# Nyan.net
KiCad netlist of a schematic drawn in EAGLE
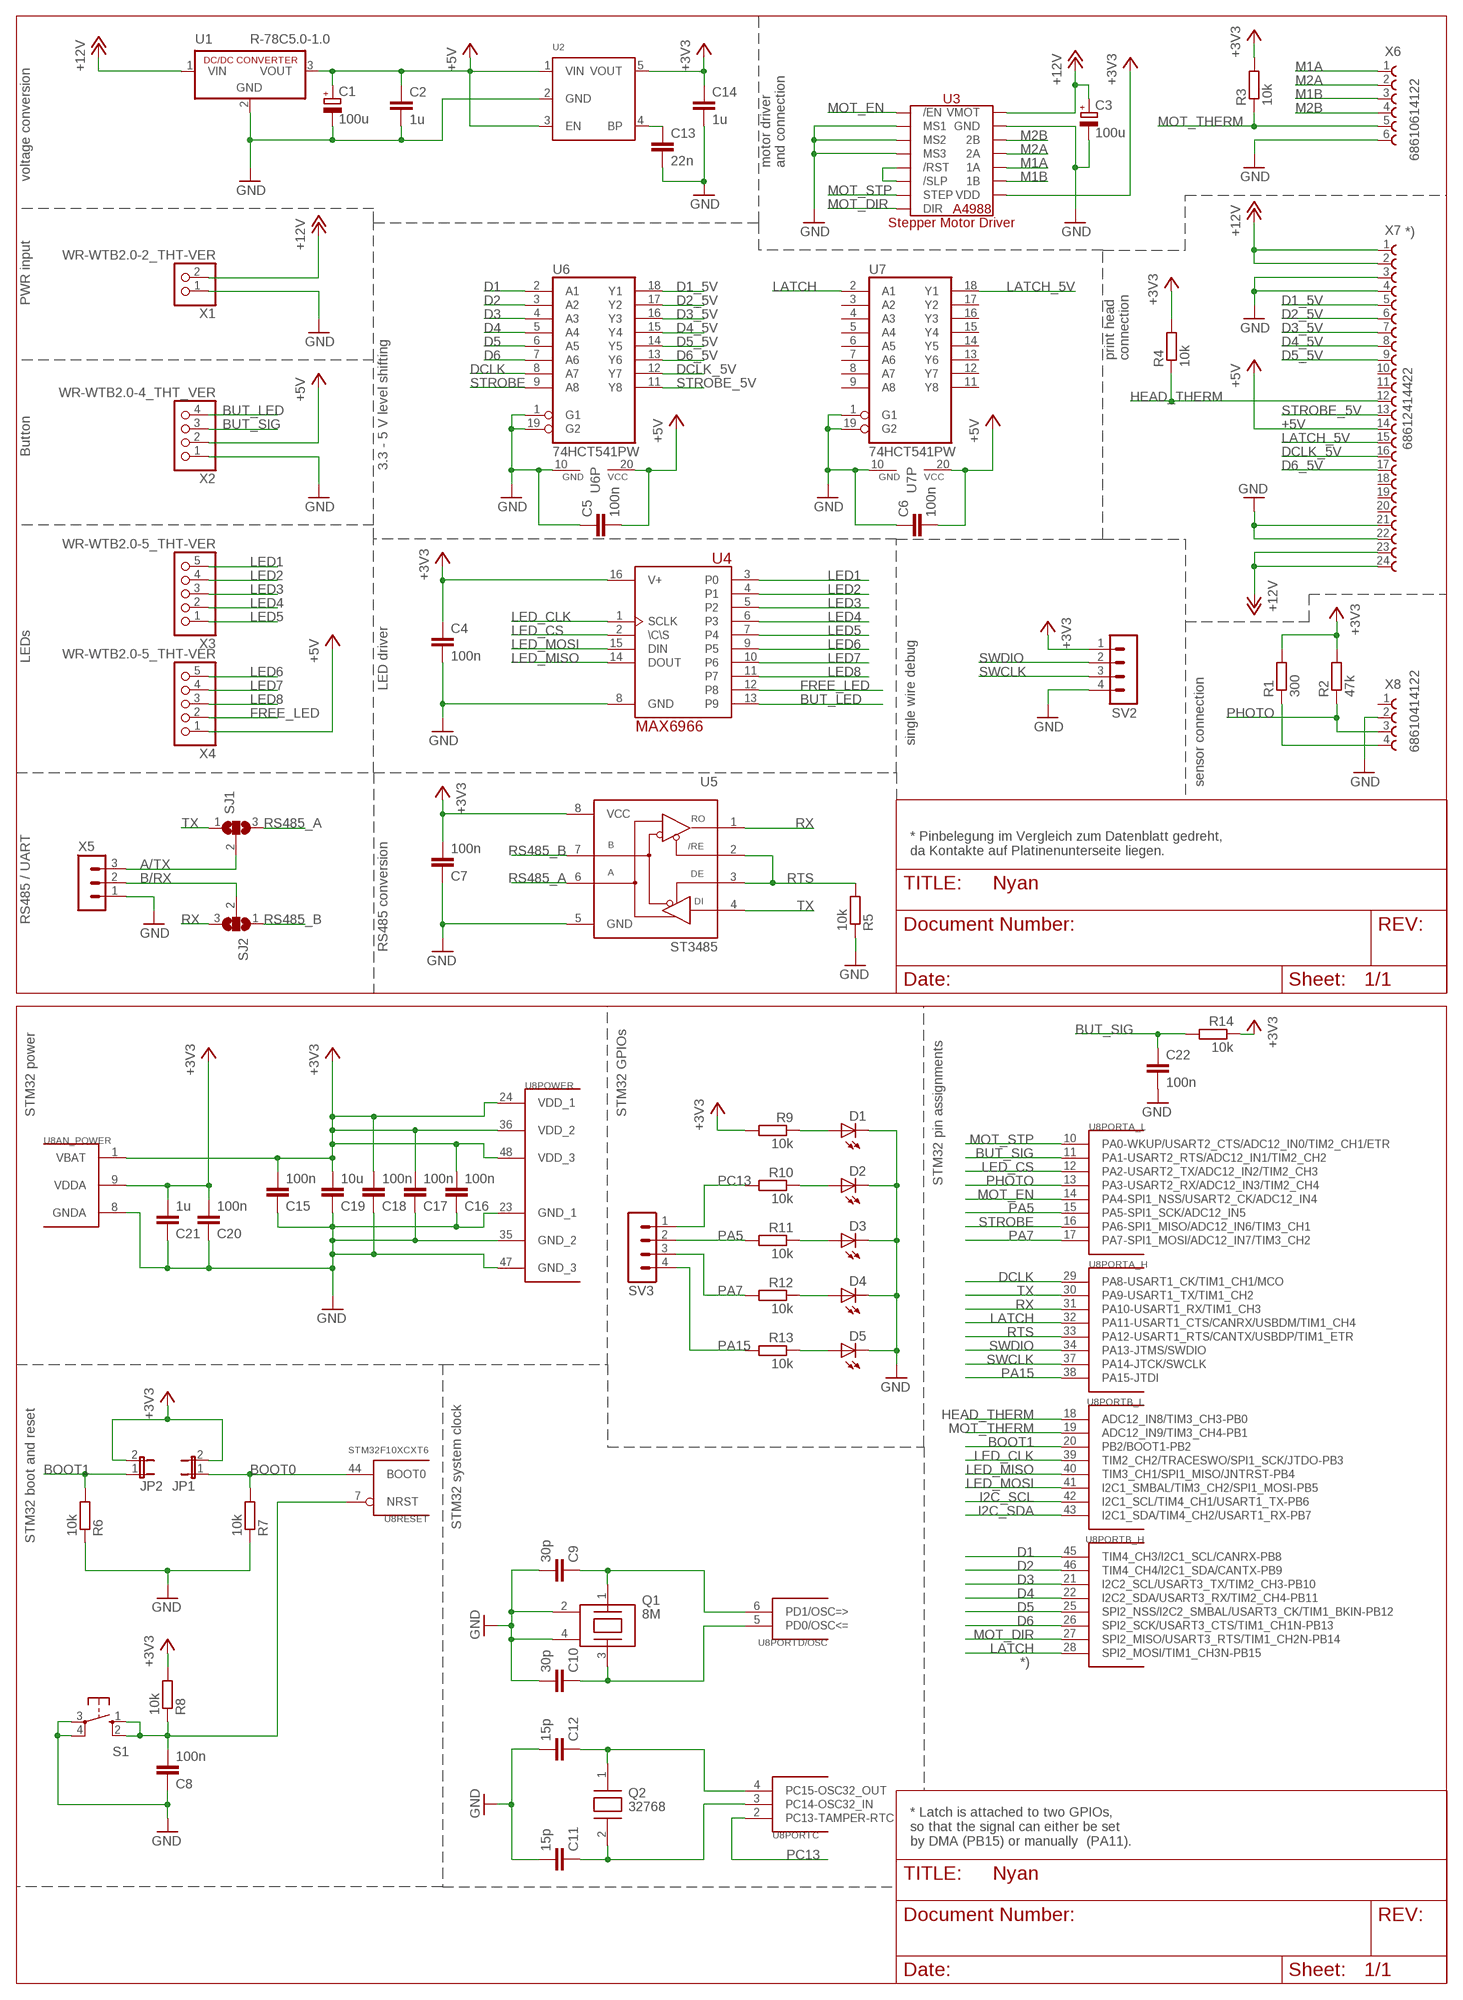
[diagram p0: schematic, sheet 1]

(export (version "E")
  (design (tool "Eeschema 10.0.6"))
  (components
    (comp (ref "C1")
      (value "100u")
      (footprint "eagle-import:E2,5-6")
      (libsource (lib "eagle-import") (part "CPOL-EUE2.5-6"))
    )
    (comp (ref "C2")
      (value "1u")
      (footprint "eagle-import:C0603")
      (libsource (lib "eagle-import") (part "C-EUC0603"))
    )
    (comp (ref "C3")
      (value "100u")
      (footprint "eagle-import:E2,5-6")
      (libsource (lib "eagle-import") (part "CPOL-EUE2.5-6"))
    )
    (comp (ref "C4")
      (value "100n")
      (footprint "eagle-import:C0603")
      (libsource (lib "eagle-import") (part "C-EUC0603"))
    )
    (comp (ref "C5")
      (value "100n")
      (footprint "eagle-import:C0603")
      (libsource (lib "eagle-import") (part "C-EUC0603"))
    )
    (comp (ref "C6")
      (value "100n")
      (footprint "eagle-import:C0603")
      (libsource (lib "eagle-import") (part "C-EUC0603"))
    )
    (comp (ref "C7")
      (value "100n")
      (footprint "eagle-import:C0603")
      (libsource (lib "eagle-import") (part "C-EUC0603"))
    )
    (comp (ref "C8")
      (value "100n")
      (footprint "eagle-import:C0603")
      (libsource (lib "eagle-import") (part "C-EUC0603"))
    )
    (comp (ref "C9")
      (value "30p")
      (footprint "eagle-import:C0603")
      (libsource (lib "eagle-import") (part "C-EUC0603"))
    )
    (comp (ref "C10")
      (value "30p")
      (footprint "eagle-import:C0603")
      (libsource (lib "eagle-import") (part "C-EUC0603"))
    )
    (comp (ref "C11")
      (value "15p")
      (footprint "eagle-import:C0603")
      (libsource (lib "eagle-import") (part "C-EUC0603"))
    )
    (comp (ref "C12")
      (value "15p")
      (footprint "eagle-import:C0603")
      (libsource (lib "eagle-import") (part "C-EUC0603"))
    )
    (comp (ref "C13")
      (value "22n")
      (footprint "eagle-import:C0603")
      (libsource (lib "eagle-import") (part "C-EUC0603"))
    )
    (comp (ref "C14")
      (value "1u")
      (footprint "eagle-import:C0603")
      (libsource (lib "eagle-import") (part "C-EUC0603"))
    )
    (comp (ref "C15")
      (value "100n")
      (footprint "eagle-import:C0603")
      (libsource (lib "eagle-import") (part "C-EUC0603"))
    )
    (comp (ref "C16")
      (value "100n")
      (footprint "eagle-import:C0603")
      (libsource (lib "eagle-import") (part "C-EUC0603"))
    )
    (comp (ref "C17")
      (value "100n")
      (footprint "eagle-import:C0603")
      (libsource (lib "eagle-import") (part "C-EUC0603"))
    )
    (comp (ref "C18")
      (value "100n")
      (footprint "eagle-import:C0603")
      (libsource (lib "eagle-import") (part "C-EUC0603"))
    )
    (comp (ref "C19")
      (value "10u")
      (footprint "eagle-import:C0603")
      (libsource (lib "eagle-import") (part "C-EUC0603"))
    )
    (comp (ref "C20")
      (value "100n")
      (footprint "eagle-import:C0603")
      (libsource (lib "eagle-import") (part "C-EUC0603"))
    )
    (comp (ref "C21")
      (value "1u")
      (footprint "eagle-import:C0603")
      (libsource (lib "eagle-import") (part "C-EUC0603"))
    )
    (comp (ref "C22")
      (value "100n")
      (footprint "eagle-import:C0603")
      (libsource (lib "eagle-import") (part "C-EUC0603"))
    )
    (comp (ref "D1")
      (value "LEDCHIP-LED0603")
      (footprint "eagle-import:CHIP-LED0603")
      (libsource (lib "eagle-import") (part "LEDCHIP-LED0603"))
    )
    (comp (ref "D2")
      (value "LEDCHIP-LED0603")
      (footprint "eagle-import:CHIP-LED0603")
      (libsource (lib "eagle-import") (part "LEDCHIP-LED0603"))
    )
    (comp (ref "D3")
      (value "LEDCHIP-LED0603")
      (footprint "eagle-import:CHIP-LED0603")
      (libsource (lib "eagle-import") (part "LEDCHIP-LED0603"))
    )
    (comp (ref "D4")
      (value "LEDCHIP-LED0603")
      (footprint "eagle-import:CHIP-LED0603")
      (libsource (lib "eagle-import") (part "LEDCHIP-LED0603"))
    )
    (comp (ref "D5")
      (value "LEDCHIP-LED0603")
      (footprint "eagle-import:CHIP-LED0603")
      (libsource (lib "eagle-import") (part "LEDCHIP-LED0603"))
    )
    (comp (ref "JP1")
      (value "JP1E")
      (footprint "eagle-import:JP1")
      (libsource (lib "eagle-import") (part "JP1E"))
    )
    (comp (ref "JP2")
      (value "JP1E")
      (footprint "eagle-import:JP1")
      (libsource (lib "eagle-import") (part "JP1E"))
    )
    (comp (ref "Q1")
      (value "8M")
      (footprint "eagle-import:SMD_5X3.2")
      (libsource (lib "eagle-import") (part "YSX531SL"))
    )
    (comp (ref "Q2")
      (value "32768")
      (footprint "eagle-import:SMD_3.2X1.5")
      (libsource (lib "eagle-import") (part "YST310S"))
    )
    (comp (ref "R1")
      (value "300")
      (footprint "eagle-import:R0603")
      (libsource (lib "eagle-import") (part "R-EU_R0603"))
    )
    (comp (ref "R2")
      (value "47k")
      (footprint "eagle-import:R0603")
      (libsource (lib "eagle-import") (part "R-EU_R0603"))
    )
    (comp (ref "R3")
      (value "10k")
      (footprint "eagle-import:R0603")
      (libsource (lib "eagle-import") (part "R-EU_R0603"))
    )
    (comp (ref "R4")
      (value "10k")
      (footprint "eagle-import:R0603")
      (libsource (lib "eagle-import") (part "R-EU_R0603"))
    )
    (comp (ref "R5")
      (value "10k")
      (footprint "eagle-import:R0603")
      (libsource (lib "eagle-import") (part "R-EU_R0603"))
    )
    (comp (ref "R6")
      (value "10k")
      (footprint "eagle-import:R0603")
      (libsource (lib "eagle-import") (part "R-EU_R0603"))
    )
    (comp (ref "R7")
      (value "10k")
      (footprint "eagle-import:R0603")
      (libsource (lib "eagle-import") (part "R-EU_R0603"))
    )
    (comp (ref "R8")
      (value "10k")
      (footprint "eagle-import:R0603")
      (libsource (lib "eagle-import") (part "R-EU_R0603"))
    )
    (comp (ref "R9")
      (value "10k")
      (footprint "eagle-import:R0603")
      (libsource (lib "eagle-import") (part "R-EU_R0603"))
    )
    (comp (ref "R10")
      (value "10k")
      (footprint "eagle-import:R0603")
      (libsource (lib "eagle-import") (part "R-EU_R0603"))
    )
    (comp (ref "R11")
      (value "10k")
      (footprint "eagle-import:R0603")
      (libsource (lib "eagle-import") (part "R-EU_R0603"))
    )
    (comp (ref "R12")
      (value "10k")
      (footprint "eagle-import:R0603")
      (libsource (lib "eagle-import") (part "R-EU_R0603"))
    )
    (comp (ref "R13")
      (value "10k")
      (footprint "eagle-import:R0603")
      (libsource (lib "eagle-import") (part "R-EU_R0603"))
    )
    (comp (ref "R14")
      (value "10k")
      (footprint "eagle-import:R0603")
      (libsource (lib "eagle-import") (part "R-EU_R0603"))
    )
    (comp (ref "S1")
      (value "6X6_MOMENTARY_SWITCH")
      (footprint "eagle-import:6X6_MOMENTARY_SWITCH")
      (libsource (lib "eagle-import") (part "6X6_MOMENTARY_SWITCH"))
    )
    (comp (ref "SJ1")
      (value "SJ2W")
      (footprint "eagle-import:SJ_2")
      (libsource (lib "eagle-import") (part "SJ2W"))
    )
    (comp (ref "SJ2")
      (value "SJ2W")
      (footprint "eagle-import:SJ_2")
      (libsource (lib "eagle-import") (part "SJ2W"))
    )
    (comp (ref "SV2")
      (value "MA04-1ROUND_PAD")
      (footprint "eagle-import:MA04-1_ROUND")
      (libsource (lib "eagle-import") (part "MA04-1ROUND_PAD"))
    )
    (comp (ref "SV3")
      (value "MA04-1ROUND_PAD")
      (footprint "eagle-import:MA04-1_ROUND")
      (libsource (lib "eagle-import") (part "MA04-1ROUND_PAD"))
    )
    (comp (ref "U1")
      (value "R-78C5.0-1.0")
      (footprint "eagle-import:SIP3")
      (libsource (lib "eagle-import") (part "R-78C-1.05.0"))
    )
    (comp (ref "U2")
      (value "RT9193")
      (footprint "eagle-import:SOT23-5")
      (libsource (lib "eagle-import") (part "RT9193"))
    )
    (comp (ref "U3")
      (value "A4988_STEP")
      (footprint "eagle-import:A4988_STEP")
      (libsource (lib "eagle-import") (part "A4988_STEP"))
    )
    (comp (ref "U4")
      (value "MAX6966")
      (footprint "eagle-import:QSOP-16")
      (libsource (lib "eagle-import") (part "MAX6966"))
    )
    (comp (ref "U5")
      (value "ST3485")
      (footprint "eagle-import:SO-08")
      (libsource (lib "eagle-import") (part "ST3485"))
    )
    (comp (ref "U6")
      (value "74HCT541PW")
      (footprint "eagle-import:TSSOP20")
      (libsource (lib "eagle-import") (part "74541PWHCT"))
    )
    (comp (ref "U7")
      (value "74HCT541PW")
      (footprint "eagle-import:TSSOP20")
      (libsource (lib "eagle-import") (part "74541PWHCT"))
    )
    (comp (ref "U8")
      (value "STM32F10XCXT6")
      (footprint "eagle-import:TQFP48")
      (libsource (lib "eagle-import") (part "STM32F10XCXT6"))
    )
    (comp (ref "X1")
      (value "WR-WTB2.0-2_THT-VER")
      (footprint "eagle-import:WR-WTB2.0-2-THT-VER")
      (libsource (lib "eagle-import") (part "WR-WTB2.0-2_THT-VER"))
    )
    (comp (ref "X2")
      (value "WR-WTB2.0-4_THT_VER")
      (footprint "eagle-import:WR-WTB2.0-4-THT-VER")
      (libsource (lib "eagle-import") (part "WR-WTB2.0-4_THT_VER"))
    )
    (comp (ref "X3")
      (value "WR-WTB2.0-5_THT-VER")
      (footprint "eagle-import:WR-WTB2.0-5-THT-VER")
      (libsource (lib "eagle-import") (part "WR-WTB2.0-5_THT-VER"))
    )
    (comp (ref "X4")
      (value "WR-WTB2.0-5_THT-VER")
      (footprint "eagle-import:WR-WTB2.0-5-THT-VER")
      (libsource (lib "eagle-import") (part "WR-WTB2.0-5_THT-VER"))
    )
    (comp (ref "X5")
      (value "MA03-1ROUND_PAD")
      (footprint "eagle-import:MA03-1_ROUND")
      (libsource (lib "eagle-import") (part "MA03-1ROUND_PAD"))
    )
    (comp (ref "X6")
      (value "68610614122")
      (footprint "eagle-import:68610614122")
      (libsource (lib "eagle-import") (part "68610614122"))
    )
    (comp (ref "X7")
      (value "68612414422")
      (footprint "eagle-import:68612414422")
      (libsource (lib "eagle-import") (part "68612414422"))
    )
    (comp (ref "X8")
      (value "68610414122")
      (footprint "eagle-import:68610414122")
      (libsource (lib "eagle-import") (part "68610414122"))
    )
  )
  (nets
    (net (code "1") (name "+3V3") (class "Default")
      (node (ref "C14") (pin "1") (pinfunction "1_1") (pintype "passive"))
      (node (ref "C15") (pin "2") (pinfunction "2_2") (pintype "passive"))
      (node (ref "C16") (pin "2") (pinfunction "2_2") (pintype "passive"))
      (node (ref "C17") (pin "2") (pinfunction "2_2") (pintype "passive"))
      (node (ref "C18") (pin "2") (pinfunction "2_2") (pintype "passive"))
      (node (ref "C19") (pin "2") (pinfunction "2_2") (pintype "passive"))
      (node (ref "C20") (pin "2") (pinfunction "2_2") (pintype "passive"))
      (node (ref "C21") (pin "2") (pinfunction "2_2") (pintype "passive"))
      (node (ref "C4") (pin "1") (pinfunction "1_1") (pintype "passive"))
      (node (ref "C7") (pin "2") (pinfunction "2_2") (pintype "passive"))
      (node (ref "JP1") (pin "2") (pinfunction "2_2") (pintype "passive"))
      (node (ref "JP2") (pin "2") (pinfunction "2_2") (pintype "passive"))
      (node (ref "R1") (pin "2") (pinfunction "2_2") (pintype "passive"))
      (node (ref "R14") (pin "1") (pinfunction "1_1") (pintype "passive"))
      (node (ref "R2") (pin "2") (pinfunction "2_2") (pintype "passive"))
      (node (ref "R3") (pin "2") (pinfunction "2_2") (pintype "passive"))
      (node (ref "R4") (pin "2") (pinfunction "2_2") (pintype "passive"))
      (node (ref "R8") (pin "2") (pinfunction "2_2") (pintype "passive"))
      (node (ref "R9") (pin "2") (pinfunction "2_2") (pintype "passive"))
      (node (ref "SV2") (pin "1") (pinfunction "1_1") (pintype "passive"))
      (node (ref "U2") (pin "5") (pinfunction "VOUT_5") (pintype "bidirectional"))
      (node (ref "U3") (pin "VDD") (pinfunction "VDD_VDD") (pintype "bidirectional"))
      (node (ref "U4") (pin "16") (pinfunction "V+_16") (pintype "power_in"))
      (node (ref "U5") (pin "8") (pinfunction "VCC_8") (pintype "power_in"))
      (node (ref "U8") (pin "1") (pinfunction "VBAT_1") (pintype "power_in"))
      (node (ref "U8") (pin "24") (pinfunction "VDD_1_24") (pintype "power_in"))
      (node (ref "U8") (pin "36") (pinfunction "VDD_2_36") (pintype "power_in"))
      (node (ref "U8") (pin "48") (pinfunction "VDD_3_48") (pintype "power_in"))
      (node (ref "U8") (pin "9") (pinfunction "VDDA_9") (pintype "power_in"))
    )
    (net (code "2") (name "+5V") (class "Default")
      (node (ref "C1") (pin "+") (pinfunction "+_+") (pintype "passive"))
      (node (ref "C2") (pin "1") (pinfunction "1_1") (pintype "passive"))
      (node (ref "C5") (pin "2") (pinfunction "2_2") (pintype "passive"))
      (node (ref "C6") (pin "2") (pinfunction "2_2") (pintype "passive"))
      (node (ref "U1") (pin "3") (pinfunction "VOUT_3") (pintype "passive"))
      (node (ref "U2") (pin "1") (pinfunction "VIN_1") (pintype "bidirectional"))
      (node (ref "U2") (pin "3") (pinfunction "EN_3") (pintype "bidirectional"))
      (node (ref "U6") (pin "20") (pinfunction "VCC_20") (pintype "power_in"))
      (node (ref "U7") (pin "20") (pinfunction "VCC_20") (pintype "power_in"))
      (node (ref "X2") (pin "2") (pinfunction "2_2") (pintype "passive"))
      (node (ref "X4") (pin "1") (pinfunction "1_1") (pintype "passive"))
      (node (ref "X7") (pin "14") (pinfunction "14_14") (pintype "passive"))
    )
    (net (code "3") (name "+12V") (class "Default")
      (node (ref "C3") (pin "+") (pinfunction "+_+") (pintype "passive"))
      (node (ref "U1") (pin "1") (pinfunction "VIN_1") (pintype "passive"))
      (node (ref "U3") (pin "VMOT") (pinfunction "VMOT_VMOT") (pintype "bidirectional"))
      (node (ref "X1") (pin "2") (pinfunction "2_2") (pintype "passive"))
      (node (ref "X7") (pin "1") (pinfunction "1_1") (pintype "passive"))
      (node (ref "X7") (pin "2") (pinfunction "2_2") (pintype "passive"))
      (node (ref "X7") (pin "23") (pinfunction "23_23") (pintype "passive"))
      (node (ref "X7") (pin "24") (pinfunction "24_24") (pintype "passive"))
    )
    (net (code "4") (name "/A{slash}TX") (class "Default")
      (node (ref "SJ1") (pin "2") (pinfunction "2_2") (pintype "passive"))
      (node (ref "X5") (pin "3") (pinfunction "3_3") (pintype "passive"))
    )
    (net (code "5") (name "/BOOT0") (class "Default")
      (node (ref "JP1") (pin "1") (pinfunction "1_1") (pintype "passive"))
      (node (ref "R7") (pin "2") (pinfunction "2_2") (pintype "passive"))
      (node (ref "U8") (pin "44") (pinfunction "BOOT0_44") (pintype "input"))
    )
    (net (code "6") (name "/BOOT1") (class "Default")
      (node (ref "JP2") (pin "1") (pinfunction "1_1") (pintype "passive"))
      (node (ref "R6") (pin "2") (pinfunction "2_2") (pintype "passive"))
      (node (ref "U8") (pin "20") (pinfunction "PB2/BOOT1-PB2_20") (pintype "bidirectional"))
    )
    (net (code "7") (name "/BUT_LED") (class "Default")
      (node (ref "U4") (pin "13") (pinfunction "P9_13") (pintype "bidirectional"))
      (node (ref "X2") (pin "4") (pinfunction "4_4") (pintype "passive"))
    )
    (net (code "8") (name "/BUT_SIG") (class "Default")
      (node (ref "C22") (pin "1") (pinfunction "1_1") (pintype "passive"))
      (node (ref "R14") (pin "2") (pinfunction "2_2") (pintype "passive"))
      (node (ref "U8") (pin "11") (pinfunction "PA1-USART2_RTS/ADC12_IN1/TIM2_CH2_11") (pintype "bidirectional"))
      (node (ref "X2") (pin "3") (pinfunction "3_3") (pintype "passive"))
    )
    (net (code "9") (name "/B{slash}RX") (class "Default")
      (node (ref "SJ2") (pin "2") (pinfunction "2_2") (pintype "passive"))
      (node (ref "X5") (pin "2") (pinfunction "2_2") (pintype "passive"))
    )
    (net (code "10") (name "/D1") (class "Default")
      (node (ref "U6") (pin "2") (pinfunction "A1_2") (pintype "input"))
      (node (ref "U8") (pin "45") (pinfunction "TIM4_CH3/I2C1_SCL/CANRX-PB8_45") (pintype "bidirectional"))
    )
    (net (code "11") (name "/D1_5V") (class "Default")
      (node (ref "U6") (pin "18") (pinfunction "Y1_18") (pintype "tri_state"))
      (node (ref "X7") (pin "5") (pinfunction "5_5") (pintype "passive"))
    )
    (net (code "12") (name "/D2") (class "Default")
      (node (ref "U6") (pin "3") (pinfunction "A2_3") (pintype "input"))
      (node (ref "U8") (pin "46") (pinfunction "TIM4_CH4/I2C1_SDA/CANTX-PB9_46") (pintype "bidirectional"))
    )
    (net (code "13") (name "/D2_5V") (class "Default")
      (node (ref "U6") (pin "17") (pinfunction "Y2_17") (pintype "tri_state"))
      (node (ref "X7") (pin "6") (pinfunction "6_6") (pintype "passive"))
    )
    (net (code "14") (name "/D3") (class "Default")
      (node (ref "U6") (pin "4") (pinfunction "A3_4") (pintype "input"))
      (node (ref "U8") (pin "21") (pinfunction "I2C2_SCL/USART3_TX/TIM2_CH3-PB10_21") (pintype "bidirectional"))
    )
    (net (code "15") (name "/D3_5V") (class "Default")
      (node (ref "U6") (pin "16") (pinfunction "Y3_16") (pintype "tri_state"))
      (node (ref "X7") (pin "7") (pinfunction "7_7") (pintype "passive"))
    )
    (net (code "16") (name "/D4") (class "Default")
      (node (ref "U6") (pin "5") (pinfunction "A4_5") (pintype "input"))
      (node (ref "U8") (pin "22") (pinfunction "I2C2_SDA/USART3_RX/TIM2_CH4-PB11_22") (pintype "bidirectional"))
    )
    (net (code "17") (name "/D4_5V") (class "Default")
      (node (ref "U6") (pin "15") (pinfunction "Y4_15") (pintype "tri_state"))
      (node (ref "X7") (pin "8") (pinfunction "8_8") (pintype "passive"))
    )
    (net (code "18") (name "/D5") (class "Default")
      (node (ref "U6") (pin "6") (pinfunction "A5_6") (pintype "input"))
      (node (ref "U8") (pin "25") (pinfunction "SPI2_NSS/I2C2_SMBAL/USART3_CK/TIM1_BKIN-PB12_25") (pintype "bidirectional"))
    )
    (net (code "19") (name "/D5_5V") (class "Default")
      (node (ref "U6") (pin "14") (pinfunction "Y5_14") (pintype "tri_state"))
      (node (ref "X7") (pin "9") (pinfunction "9_9") (pintype "passive"))
    )
    (net (code "20") (name "/D6") (class "Default")
      (node (ref "U6") (pin "7") (pinfunction "A6_7") (pintype "input"))
      (node (ref "U8") (pin "26") (pinfunction "SPI2_SCK/USART3_CTS/TIM1_CH1N-PB13_26") (pintype "bidirectional"))
    )
    (net (code "21") (name "/D6_5V") (class "Default")
      (node (ref "U6") (pin "13") (pinfunction "Y6_13") (pintype "tri_state"))
      (node (ref "X7") (pin "17") (pinfunction "17_17") (pintype "passive"))
    )
    (net (code "22") (name "/DCLK") (class "Default")
      (node (ref "U6") (pin "8") (pinfunction "A7_8") (pintype "input"))
      (node (ref "U8") (pin "29") (pinfunction "PA8-USART1_CK/TIM1_CH1/MCO_29") (pintype "bidirectional"))
    )
    (net (code "23") (name "/DCLK_5V") (class "Default")
      (node (ref "U6") (pin "12") (pinfunction "Y7_12") (pintype "tri_state"))
      (node (ref "X7") (pin "16") (pinfunction "16_16") (pintype "passive"))
    )
    (net (code "24") (name "/FREE_LED") (class "Default")
      (node (ref "U4") (pin "12") (pinfunction "P8_12") (pintype "bidirectional"))
      (node (ref "X4") (pin "2") (pinfunction "2_2") (pintype "passive"))
    )
    (net (code "25") (name "/HEAD_THERM") (class "Default")
      (node (ref "R4") (pin "1") (pinfunction "1_1") (pintype "passive"))
      (node (ref "U8") (pin "18") (pinfunction "ADC12_IN8/TIM3_CH3-PB0_18") (pintype "bidirectional"))
      (node (ref "X7") (pin "12") (pinfunction "12_12") (pintype "passive"))
    )
    (net (code "26") (name "/I2C_SCL") (class "Default")
      (node (ref "U8") (pin "42") (pinfunction "I2C1_SCL/TIM4_CH1/USART1_TX-PB6_42") (pintype "bidirectional"))
    )
    (net (code "27") (name "/I2C_SDA") (class "Default")
      (node (ref "U8") (pin "43") (pinfunction "I2C1_SDA/TIM4_CH2/USART1_RX-PB7_43") (pintype "bidirectional"))
    )
    (net (code "28") (name "/LATCH") (class "Default")
      (node (ref "U7") (pin "2") (pinfunction "A1_2") (pintype "input"))
      (node (ref "U8") (pin "28") (pinfunction "SPI2_MOSI/TIM1_CH3N-PB15_28") (pintype "bidirectional"))
      (node (ref "U8") (pin "32") (pinfunction "PA11-USART1_CTS/CANRX/USBDM/TIM1_CH4_32") (pintype "bidirectional"))
    )
    (net (code "29") (name "/LATCH_5V") (class "Default")
      (node (ref "U7") (pin "18") (pinfunction "Y1_18") (pintype "tri_state"))
      (node (ref "X7") (pin "15") (pinfunction "15_15") (pintype "passive"))
    )
    (net (code "30") (name "/LED1") (class "Default")
      (node (ref "U4") (pin "3") (pinfunction "P0_3") (pintype "bidirectional"))
      (node (ref "X3") (pin "5") (pinfunction "5_5") (pintype "passive"))
    )
    (net (code "31") (name "/LED2") (class "Default")
      (node (ref "U4") (pin "4") (pinfunction "P1_4") (pintype "bidirectional"))
      (node (ref "X3") (pin "4") (pinfunction "4_4") (pintype "passive"))
    )
    (net (code "32") (name "/LED3") (class "Default")
      (node (ref "U4") (pin "5") (pinfunction "P2_5") (pintype "bidirectional"))
      (node (ref "X3") (pin "3") (pinfunction "3_3") (pintype "passive"))
    )
    (net (code "33") (name "/LED4") (class "Default")
      (node (ref "U4") (pin "6") (pinfunction "P3_6") (pintype "bidirectional"))
      (node (ref "X3") (pin "2") (pinfunction "2_2") (pintype "passive"))
    )
    (net (code "34") (name "/LED5") (class "Default")
      (node (ref "U4") (pin "7") (pinfunction "P4_7") (pintype "bidirectional"))
      (node (ref "X3") (pin "1") (pinfunction "1_1") (pintype "passive"))
    )
    (net (code "35") (name "/LED6") (class "Default")
      (node (ref "U4") (pin "9") (pinfunction "P5_9") (pintype "bidirectional"))
      (node (ref "X4") (pin "5") (pinfunction "5_5") (pintype "passive"))
    )
    (net (code "36") (name "/LED7") (class "Default")
      (node (ref "U4") (pin "10") (pinfunction "P6_10") (pintype "bidirectional"))
      (node (ref "X4") (pin "4") (pinfunction "4_4") (pintype "passive"))
    )
    (net (code "37") (name "/LED8") (class "Default")
      (node (ref "U4") (pin "11") (pinfunction "P7_11") (pintype "bidirectional"))
      (node (ref "X4") (pin "3") (pinfunction "3_3") (pintype "passive"))
    )
    (net (code "38") (name "/LED_CLK") (class "Default")
      (node (ref "U4") (pin "1") (pinfunction "SCLK_1") (pintype "input"))
      (node (ref "U8") (pin "39") (pinfunction "TIM2_CH2/TRACESWO/SPI1_SCK/JTDO-PB3_39") (pintype "bidirectional"))
    )
    (net (code "39") (name "/LED_CS") (class "Default")
      (node (ref "U4") (pin "2") (pinfunction "\\C\\S_2") (pintype "input"))
      (node (ref "U8") (pin "12") (pinfunction "PA2-USART2_TX/ADC12_IN2/TIM2_CH3_12") (pintype "bidirectional"))
    )
    (net (code "40") (name "/LED_MISO") (class "Default")
      (node (ref "U4") (pin "14") (pinfunction "DOUT_14") (pintype "output"))
      (node (ref "U8") (pin "40") (pinfunction "TIM3_CH1/SPI1_MISO/JNTRST-PB4_40") (pintype "bidirectional"))
    )
    (net (code "41") (name "/LED_MOSI") (class "Default")
      (node (ref "U4") (pin "15") (pinfunction "DIN_15") (pintype "input"))
      (node (ref "U8") (pin "41") (pinfunction "I2C1_SMBAL/TIM3_CH2/SPI1_MOSI-PB5_41") (pintype "bidirectional"))
    )
    (net (code "42") (name "/M1A") (class "Default")
      (node (ref "U3") (pin "1A") (pinfunction "1A_1A") (pintype "bidirectional"))
      (node (ref "X6") (pin "1") (pinfunction "1_1") (pintype "passive"))
    )
    (net (code "43") (name "/M1B") (class "Default")
      (node (ref "U3") (pin "1B") (pinfunction "1B_1B") (pintype "bidirectional"))
      (node (ref "X6") (pin "3") (pinfunction "3_3") (pintype "passive"))
    )
    (net (code "44") (name "/M2A") (class "Default")
      (node (ref "U3") (pin "2A") (pinfunction "2A_2A") (pintype "bidirectional"))
      (node (ref "X6") (pin "2") (pinfunction "2_2") (pintype "passive"))
    )
    (net (code "45") (name "/M2B") (class "Default")
      (node (ref "U3") (pin "2B") (pinfunction "2B_2B") (pintype "bidirectional"))
      (node (ref "X6") (pin "4") (pinfunction "4_4") (pintype "passive"))
    )
    (net (code "46") (name "/MOT_DIR") (class "Default")
      (node (ref "U3") (pin "DIR") (pinfunction "DIR_DIR") (pintype "bidirectional"))
      (node (ref "U8") (pin "27") (pinfunction "SPI2_MISO/USART3_RTS/TIM1_CH2N-PB14_27") (pintype "bidirectional"))
    )
    (net (code "47") (name "/MOT_EN") (class "Default")
      (node (ref "U3") (pin "/EN") (pinfunction "/EN_/EN") (pintype "bidirectional"))
      (node (ref "U8") (pin "14") (pinfunction "PA4-SPI1_NSS/USART2_CK/ADC12_IN4_14") (pintype "bidirectional"))
    )
    (net (code "48") (name "/MOT_STP") (class "Default")
      (node (ref "U3") (pin "STEP") (pinfunction "STEP_STEP") (pintype "bidirectional"))
      (node (ref "U8") (pin "10") (pinfunction "PA0-WKUP/USART2_CTS/ADC12_IN0/TIM2_CH1/ETR_10") (pintype "bidirectional"))
    )
    (net (code "49") (name "/MOT_THERM") (class "Default")
      (node (ref "R3") (pin "1") (pinfunction "1_1") (pintype "passive"))
      (node (ref "U8") (pin "19") (pinfunction "ADC12_IN9/TIM3_CH4-PB1_19") (pintype "bidirectional"))
      (node (ref "X6") (pin "5") (pinfunction "5_5") (pintype "passive"))
    )
    (net (code "50") (name "/PA5") (class "Default")
      (node (ref "R11") (pin "2") (pinfunction "2_2") (pintype "passive"))
      (node (ref "SV3") (pin "2") (pinfunction "2_2") (pintype "passive"))
      (node (ref "U8") (pin "15") (pinfunction "PA5-SPI1_SCK/ADC12_IN5_15") (pintype "bidirectional"))
    )
    (net (code "51") (name "/PA7") (class "Default")
      (node (ref "R12") (pin "2") (pinfunction "2_2") (pintype "passive"))
      (node (ref "SV3") (pin "3") (pinfunction "3_3") (pintype "passive"))
      (node (ref "U8") (pin "17") (pinfunction "PA7-SPI1_MOSI/ADC12_IN7/TIM3_CH2_17") (pintype "bidirectional"))
    )
    (net (code "52") (name "/PA15") (class "Default")
      (node (ref "R13") (pin "2") (pinfunction "2_2") (pintype "passive"))
      (node (ref "SV3") (pin "4") (pinfunction "4_4") (pintype "passive"))
      (node (ref "U8") (pin "38") (pinfunction "PA15-JTDI_38") (pintype "bidirectional"))
    )
    (net (code "53") (name "/PC13") (class "Default")
      (node (ref "R10") (pin "2") (pinfunction "2_2") (pintype "passive"))
      (node (ref "SV3") (pin "1") (pinfunction "1_1") (pintype "passive"))
      (node (ref "U8") (pin "2") (pinfunction "PC13-TAMPER-RTC_2") (pintype "bidirectional"))
    )
    (net (code "54") (name "/PHOTO") (class "Default")
      (node (ref "R2") (pin "1") (pinfunction "1_1") (pintype "passive"))
      (node (ref "U8") (pin "13") (pinfunction "PA3-USART2_RX/ADC12_IN3/TIM2_CH4_13") (pintype "bidirectional"))
      (node (ref "X8") (pin "3") (pinfunction "3_3") (pintype "passive"))
    )
    (net (code "55") (name "/RS485_A") (class "Default")
      (node (ref "SJ1") (pin "3") (pinfunction "3_3") (pintype "passive"))
      (node (ref "U5") (pin "6") (pinfunction "A_6") (pintype "open_collector"))
    )
    (net (code "56") (name "/RS485_B") (class "Default")
      (node (ref "SJ2") (pin "1") (pinfunction "1_1") (pintype "passive"))
      (node (ref "U5") (pin "7") (pinfunction "B_7") (pintype "open_collector"))
    )
    (net (code "57") (name "/RTS") (class "Default")
      (node (ref "R5") (pin "2") (pinfunction "2_2") (pintype "passive"))
      (node (ref "U5") (pin "2") (pinfunction "~{RE}_2") (pintype "input"))
      (node (ref "U5") (pin "3") (pinfunction "DE_3") (pintype "input"))
      (node (ref "U8") (pin "33") (pinfunction "PA12-USART1_RTS/CANTX/USBDP/TIM1_ETR_33") (pintype "bidirectional"))
    )
    (net (code "58") (name "/RX") (class "Default")
      (node (ref "SJ2") (pin "3") (pinfunction "3_3") (pintype "passive"))
      (node (ref "U5") (pin "1") (pinfunction "RO_1") (pintype "output"))
      (node (ref "U8") (pin "31") (pinfunction "PA10-USART1_RX/TIM1_CH3_31") (pintype "bidirectional"))
    )
    (net (code "59") (name "/STROBE") (class "Default")
      (node (ref "U6") (pin "9") (pinfunction "A8_9") (pintype "input"))
      (node (ref "U8") (pin "16") (pinfunction "PA6-SPI1_MISO/ADC12_IN6/TIM3_CH1_16") (pintype "bidirectional"))
    )
    (net (code "60") (name "/STROBE_5V") (class "Default")
      (node (ref "U6") (pin "11") (pinfunction "Y8_11") (pintype "tri_state"))
      (node (ref "X7") (pin "13") (pinfunction "13_13") (pintype "passive"))
    )
    (net (code "61") (name "/SWCLK") (class "Default")
      (node (ref "SV2") (pin "3") (pinfunction "3_3") (pintype "passive"))
      (node (ref "U8") (pin "37") (pinfunction "PA14-JTCK/SWCLK_37") (pintype "bidirectional"))
    )
    (net (code "62") (name "/SWDIO") (class "Default")
      (node (ref "SV2") (pin "2") (pinfunction "2_2") (pintype "passive"))
      (node (ref "U8") (pin "34") (pinfunction "PA13-JTMS/SWDIO_34") (pintype "bidirectional"))
    )
    (net (code "63") (name "/TX") (class "Default")
      (node (ref "SJ1") (pin "1") (pinfunction "1_1") (pintype "passive"))
      (node (ref "U5") (pin "4") (pinfunction "DI_4") (pintype "input"))
      (node (ref "U8") (pin "30") (pinfunction "PA9-USART1_TX/TIM1_CH2_30") (pintype "bidirectional"))
    )
    (net (code "64") (name "GND") (class "Default")
      (node (ref "C1") (pin "-") (pinfunction "-_-") (pintype "passive"))
      (node (ref "C10") (pin "2") (pinfunction "2_2") (pintype "passive"))
      (node (ref "C11") (pin "2") (pinfunction "2_2") (pintype "passive"))
      (node (ref "C12") (pin "2") (pinfunction "2_2") (pintype "passive"))
      (node (ref "C13") (pin "2") (pinfunction "2_2") (pintype "passive"))
      (node (ref "C14") (pin "2") (pinfunction "2_2") (pintype "passive"))
      (node (ref "C15") (pin "1") (pinfunction "1_1") (pintype "passive"))
      (node (ref "C16") (pin "1") (pinfunction "1_1") (pintype "passive"))
      (node (ref "C17") (pin "1") (pinfunction "1_1") (pintype "passive"))
      (node (ref "C18") (pin "1") (pinfunction "1_1") (pintype "passive"))
      (node (ref "C19") (pin "1") (pinfunction "1_1") (pintype "passive"))
      (node (ref "C2") (pin "2") (pinfunction "2_2") (pintype "passive"))
      (node (ref "C20") (pin "1") (pinfunction "1_1") (pintype "passive"))
      (node (ref "C21") (pin "1") (pinfunction "1_1") (pintype "passive"))
      (node (ref "C22") (pin "2") (pinfunction "2_2") (pintype "passive"))
      (node (ref "C3") (pin "-") (pinfunction "-_-") (pintype "passive"))
      (node (ref "C4") (pin "2") (pinfunction "2_2") (pintype "passive"))
      (node (ref "C5") (pin "1") (pinfunction "1_1") (pintype "passive"))
      (node (ref "C6") (pin "1") (pinfunction "1_1") (pintype "passive"))
      (node (ref "C7") (pin "1") (pinfunction "1_1") (pintype "passive"))
      (node (ref "C8") (pin "1") (pinfunction "1_1") (pintype "passive"))
      (node (ref "C9") (pin "2") (pinfunction "2_2") (pintype "passive"))
      (node (ref "D1") (pin "C") (pinfunction "C_C") (pintype "passive"))
      (node (ref "D2") (pin "C") (pinfunction "C_C") (pintype "passive"))
      (node (ref "D3") (pin "C") (pinfunction "C_C") (pintype "passive"))
      (node (ref "D4") (pin "C") (pinfunction "C_C") (pintype "passive"))
      (node (ref "D5") (pin "C") (pinfunction "C_C") (pintype "passive"))
      (node (ref "Q1") (pin "2") (pinfunction "2_2") (pintype "bidirectional"))
      (node (ref "Q1") (pin "4") (pinfunction "4_4") (pintype "bidirectional"))
      (node (ref "R5") (pin "1") (pinfunction "1_1") (pintype "passive"))
      (node (ref "R6") (pin "1") (pinfunction "1_1") (pintype "passive"))
      (node (ref "R7") (pin "1") (pinfunction "1_1") (pintype "passive"))
      (node (ref "S1") (pin "3") (pinfunction "3_3") (pintype "passive"))
      (node (ref "S1") (pin "4") (pinfunction "4_4") (pintype "passive"))
      (node (ref "SV2") (pin "4") (pinfunction "4_4") (pintype "passive"))
      (node (ref "U1") (pin "2") (pinfunction "GND_2") (pintype "passive"))
      (node (ref "U2") (pin "2") (pinfunction "GND_2") (pintype "bidirectional"))
      (node (ref "U3") (pin "GND") (pinfunction "GND_GND") (pintype "bidirectional"))
      (node (ref "U3") (pin "GND2") (pinfunction "GND_GND2") (pintype "bidirectional"))
      (node (ref "U3") (pin "MS1") (pinfunction "MS1_MS1") (pintype "bidirectional"))
      (node (ref "U3") (pin "MS2") (pinfunction "MS2_MS2") (pintype "bidirectional"))
      (node (ref "U3") (pin "MS3") (pinfunction "MS3_MS3") (pintype "bidirectional"))
      (node (ref "U4") (pin "8") (pinfunction "GND_8") (pintype "power_in"))
      (node (ref "U5") (pin "5") (pinfunction "GND_5") (pintype "power_in"))
      (node (ref "U6") (pin "1") (pinfunction "G1_1") (pintype "input"))
      (node (ref "U6") (pin "10") (pinfunction "GND_10") (pintype "power_in"))
      (node (ref "U6") (pin "19") (pinfunction "G2_19") (pintype "input"))
      (node (ref "U7") (pin "1") (pinfunction "G1_1") (pintype "input"))
      (node (ref "U7") (pin "10") (pinfunction "GND_10") (pintype "power_in"))
      (node (ref "U7") (pin "19") (pinfunction "G2_19") (pintype "input"))
      (node (ref "U8") (pin "23") (pinfunction "GND_1_23") (pintype "power_in"))
      (node (ref "U8") (pin "35") (pinfunction "GND_2_35") (pintype "power_in"))
      (node (ref "U8") (pin "47") (pinfunction "GND_3_47") (pintype "power_in"))
      (node (ref "U8") (pin "8") (pinfunction "GNDA_8") (pintype "power_in"))
      (node (ref "X1") (pin "1") (pinfunction "1_1") (pintype "passive"))
      (node (ref "X2") (pin "1") (pinfunction "1_1") (pintype "passive"))
      (node (ref "X5") (pin "1") (pinfunction "1_1") (pintype "passive"))
      (node (ref "X6") (pin "6") (pinfunction "6_6") (pintype "passive"))
      (node (ref "X7") (pin "21") (pinfunction "21_21") (pintype "passive"))
      (node (ref "X7") (pin "22") (pinfunction "22_22") (pintype "passive"))
      (node (ref "X7") (pin "3") (pinfunction "3_3") (pintype "passive"))
      (node (ref "X7") (pin "4") (pinfunction "4_4") (pintype "passive"))
      (node (ref "X8") (pin "2") (pinfunction "2_2") (pintype "passive"))
    )
    (net (code "65") (name "Net-(D1-PadA)") (class "Default")
      (node (ref "D1") (pin "A") (pinfunction "A_A") (pintype "passive"))
      (node (ref "R9") (pin "1") (pinfunction "1_1") (pintype "passive"))
    )
    (net (code "66") (name "Net-(D2-PadA)") (class "Default")
      (node (ref "D2") (pin "A") (pinfunction "A_A") (pintype "passive"))
      (node (ref "R10") (pin "1") (pinfunction "1_1") (pintype "passive"))
    )
    (net (code "67") (name "Net-(D3-PadA)") (class "Default")
      (node (ref "D3") (pin "A") (pinfunction "A_A") (pintype "passive"))
      (node (ref "R11") (pin "1") (pinfunction "1_1") (pintype "passive"))
    )
    (net (code "68") (name "Net-(D4-PadA)") (class "Default")
      (node (ref "D4") (pin "A") (pinfunction "A_A") (pintype "passive"))
      (node (ref "R12") (pin "1") (pinfunction "1_1") (pintype "passive"))
    )
    (net (code "69") (name "Net-(D5-PadA)") (class "Default")
      (node (ref "D5") (pin "A") (pinfunction "A_A") (pintype "passive"))
      (node (ref "R13") (pin "1") (pinfunction "1_1") (pintype "passive"))
    )
    (net (code "70") (name "Net-(R1-Pad1)") (class "Default")
      (node (ref "R1") (pin "1") (pinfunction "1_1") (pintype "passive"))
      (node (ref "X8") (pin "4") (pinfunction "4_4") (pintype "passive"))
    )
    (net (code "71") (name "Net-(U2-BP)") (class "Default")
      (node (ref "C13") (pin "1") (pinfunction "1_1") (pintype "passive"))
      (node (ref "U2") (pin "4") (pinfunction "BP_4") (pintype "bidirectional"))
    )
    (net (code "72") (name "Net-(U3-Pad{slash}RST)") (class "Default")
      (node (ref "U3") (pin "/RST") (pinfunction "/RST_/RST") (pintype "bidirectional"))
      (node (ref "U3") (pin "/SLP") (pinfunction "/SLP_/SLP") (pintype "bidirectional"))
    )
    (net (code "73") (name "Net-(U8F-PC14-OSC32_IN)") (class "Default")
      (node (ref "C11") (pin "1") (pinfunction "1_1") (pintype "passive"))
      (node (ref "Q2") (pin "2") (pinfunction "2_2") (pintype "bidirectional"))
      (node (ref "U8") (pin "3") (pinfunction "PC14-OSC32_IN_3") (pintype "bidirectional"))
    )
    (net (code "74") (name "Net-(U8F-PC15-OSC32_OUT)") (class "Default")
      (node (ref "C12") (pin "1") (pinfunction "1_1") (pintype "passive"))
      (node (ref "Q2") (pin "1") (pinfunction "1_1") (pintype "bidirectional"))
      (node (ref "U8") (pin "4") (pinfunction "PC15-OSC32_OUT_4") (pintype "bidirectional"))
    )
    (net (code "75") (name "Net-(U8G-PD0{slash}OSC<=)") (class "Default")
      (node (ref "C10") (pin "1") (pinfunction "1_1") (pintype "passive"))
      (node (ref "Q1") (pin "3") (pinfunction "3_3") (pintype "bidirectional"))
      (node (ref "U8") (pin "5") (pinfunction "PD0/OSC<=_5") (pintype "bidirectional"))
    )
    (net (code "76") (name "Net-(U8G-PD1{slash}OSC=>)") (class "Default")
      (node (ref "C9") (pin "1") (pinfunction "1_1") (pintype "passive"))
      (node (ref "Q1") (pin "1") (pinfunction "1_1") (pintype "bidirectional"))
      (node (ref "U8") (pin "6") (pinfunction "PD1/OSC=>_6") (pintype "bidirectional"))
    )
    (net (code "77") (name "Net-(U8I-NRST)") (class "Default")
      (node (ref "C8") (pin "2") (pinfunction "2_2") (pintype "passive"))
      (node (ref "R8") (pin "1") (pinfunction "1_1") (pintype "passive"))
      (node (ref "S1") (pin "1") (pinfunction "1_1") (pintype "passive"))
      (node (ref "S1") (pin "2") (pinfunction "2_2") (pintype "passive"))
      (node (ref "U8") (pin "7") (pinfunction "NRST_7") (pintype "input"))
    )
    (net (code "78") (name "unconnected-(U7A-A2-Pad3)") (class "Default")
      (node (ref "U7") (pin "3") (pinfunction "A2_3") (pintype "input"))
    )
    (net (code "79") (name "unconnected-(U7A-A3-Pad4)") (class "Default")
      (node (ref "U7") (pin "4") (pinfunction "A3_4") (pintype "input"))
    )
    (net (code "80") (name "unconnected-(U7A-A4-Pad5)") (class "Default")
      (node (ref "U7") (pin "5") (pinfunction "A4_5") (pintype "input"))
    )
    (net (code "81") (name "unconnected-(U7A-A5-Pad6)") (class "Default")
      (node (ref "U7") (pin "6") (pinfunction "A5_6") (pintype "input"))
    )
    (net (code "82") (name "unconnected-(U7A-A6-Pad7)") (class "Default")
      (node (ref "U7") (pin "7") (pinfunction "A6_7") (pintype "input"))
    )
    (net (code "83") (name "unconnected-(U7A-A7-Pad8)") (class "Default")
      (node (ref "U7") (pin "8") (pinfunction "A7_8") (pintype "input"))
    )
    (net (code "84") (name "unconnected-(U7A-A8-Pad9)") (class "Default")
      (node (ref "U7") (pin "9") (pinfunction "A8_9") (pintype "input"))
    )
    (net (code "85") (name "unconnected-(U7A-Y2-Pad17)") (class "Default")
      (node (ref "U7") (pin "17") (pinfunction "Y2_17") (pintype "tri_state"))
    )
    (net (code "86") (name "unconnected-(U7A-Y3-Pad16)") (class "Default")
      (node (ref "U7") (pin "16") (pinfunction "Y3_16") (pintype "tri_state"))
    )
    (net (code "87") (name "unconnected-(U7A-Y4-Pad15)") (class "Default")
      (node (ref "U7") (pin "15") (pinfunction "Y4_15") (pintype "tri_state"))
    )
    (net (code "88") (name "unconnected-(U7A-Y5-Pad14)") (class "Default")
      (node (ref "U7") (pin "14") (pinfunction "Y5_14") (pintype "tri_state"))
    )
    (net (code "89") (name "unconnected-(U7A-Y6-Pad13)") (class "Default")
      (node (ref "U7") (pin "13") (pinfunction "Y6_13") (pintype "tri_state"))
    )
    (net (code "90") (name "unconnected-(U7A-Y7-Pad12)") (class "Default")
      (node (ref "U7") (pin "12") (pinfunction "Y7_12") (pintype "tri_state"))
    )
    (net (code "91") (name "unconnected-(U7A-Y8-Pad11)") (class "Default")
      (node (ref "U7") (pin "11") (pinfunction "Y8_11") (pintype "tri_state"))
    )
    (net (code "92") (name "unconnected-(X7-Pad10)") (class "Default")
      (node (ref "X7") (pin "10") (pinfunction "10_10") (pintype "passive"))
    )
    (net (code "93") (name "unconnected-(X7-Pad11)") (class "Default")
      (node (ref "X7") (pin "11") (pinfunction "11_11") (pintype "passive"))
    )
    (net (code "94") (name "unconnected-(X7-Pad18)") (class "Default")
      (node (ref "X7") (pin "18") (pinfunction "18_18") (pintype "passive"))
    )
    (net (code "95") (name "unconnected-(X7-Pad19)") (class "Default")
      (node (ref "X7") (pin "19") (pinfunction "19_19") (pintype "passive"))
    )
    (net (code "96") (name "unconnected-(X7-Pad20)") (class "Default")
      (node (ref "X7") (pin "20") (pinfunction "20_20") (pintype "passive"))
    )
    (net (code "97") (name "unconnected-(X8-Pad1)") (class "Default")
      (node (ref "X8") (pin "1") (pinfunction "1_1") (pintype "passive"))
    )
  )
)
